# SCH_mini-arcade_2026-02-04.net
KiCad netlist of a schematic drawn in EasyEDA
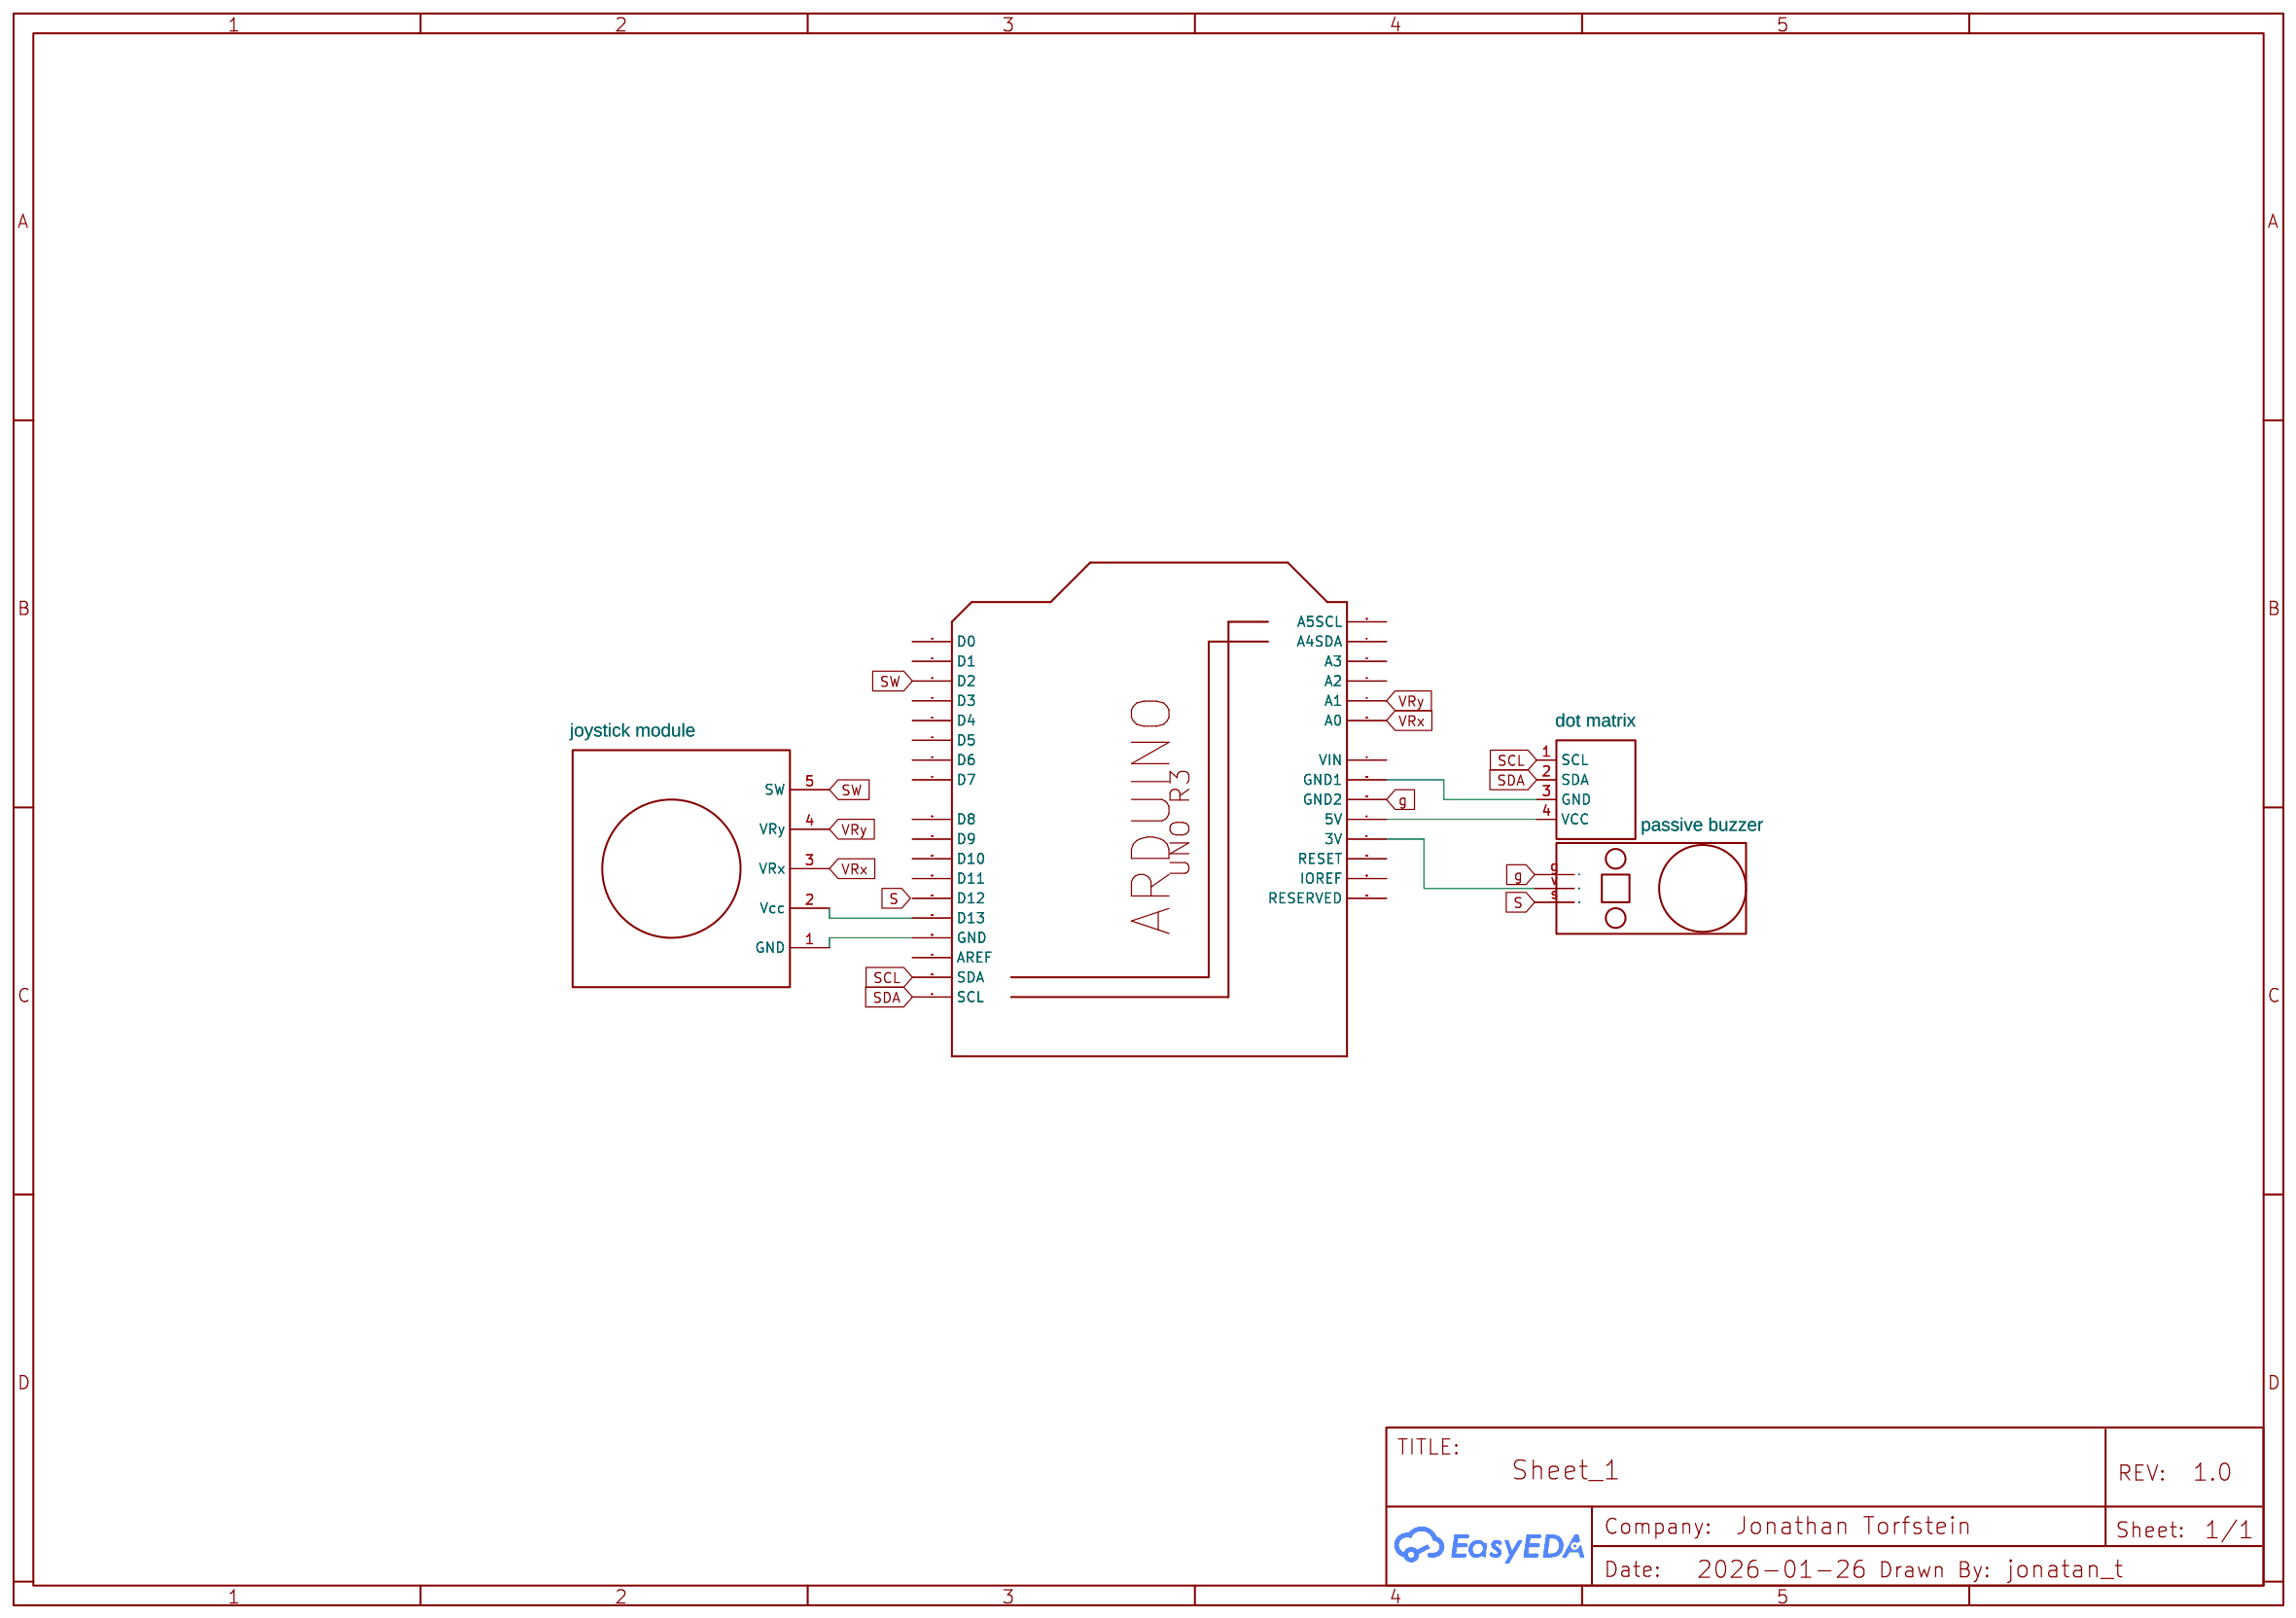
[diagram p0: schematic sheet]

(export (version "E")
  (design (tool "Eeschema 10.0.6"))
  (components
    (comp (ref "U1") (value "ARDUINOR3-DIMENSION") (libsource (lib "") (part "ARDUINOR3-DIMENSION")))
    (comp (ref "U2")
      (value "dot matrix")
      (fields
        (field (name "Manufacturer Part") "350424-1")
        (field (name "Manufacturer") "TE Connectivity(泰科电子)")
      )
      (libsource (lib "") (part "350424-1"))
    )
    (comp (ref "U3") (value "joystick module") (libsource (lib "") (part "HW-504JOYSTICK")))
    (comp (ref "U4") (value "passive buzzer") (libsource (lib "") (part "keystudio passive buzzer")))
  )
  (nets
    (net (code "1") (name "Net-(U2-GND)") (class "Default")
      (node (ref "U1") (pin "GND1") (pinfunction "GND1_GND1") (pintype "passive"))
      (node (ref "U2") (pin "3") (pinfunction "GND_3") (pintype "unspecified"))
    )
    (net (code "2") (name "Net-(U2-VCC)") (class "Default")
      (node (ref "U1") (pin "5V") (pinfunction "5V_5V") (pintype "passive"))
      (node (ref "U2") (pin "4") (pinfunction "VCC_4") (pintype "unspecified"))
    )
    (net (code "3") (name "Net-(U3-GND)") (class "Default")
      (node (ref "U1") (pin "GND") (pinfunction "GND_GND") (pintype "passive"))
      (node (ref "U3") (pin "1") (pinfunction "GND_1") (pintype "unspecified"))
    )
    (net (code "4") (name "Net-(U3-Vcc)") (class "Default")
      (node (ref "U1") (pin "D13") (pinfunction "D13_D13") (pintype "unspecified"))
      (node (ref "U3") (pin "2") (pinfunction "Vcc_2") (pintype "unspecified"))
    )
    (net (code "5") (name "Net-(U4-2)") (class "Default")
      (node (ref "U1") (pin "3V") (pinfunction "3V_3V") (pintype "passive"))
      (node (ref "U4") (pin "v") (pinfunction "2_v") (pintype "unspecified"))
    )
    (net (code "6") (name "S") (class "Default")
      (node (ref "U4") (pin "s") (pinfunction "3_s") (pintype "unspecified"))
    )
    (net (code "7") (name "SCL") (class "Default")
      (node (ref "U1") (pin "SDA") (pinfunction "SDA_SDA") (pintype "unspecified"))
      (node (ref "U2") (pin "1") (pinfunction "SCL_1") (pintype "unspecified"))
    )
    (net (code "8") (name "SDA") (class "Default")
      (node (ref "U1") (pin "SCL") (pinfunction "SCL_SCL") (pintype "unspecified"))
      (node (ref "U2") (pin "2") (pinfunction "SDA_2") (pintype "unspecified"))
    )
    (net (code "9") (name "SW") (class "Default")
      (node (ref "U1") (pin "D2") (pinfunction "D2_D2") (pintype "unspecified"))
      (node (ref "U3") (pin "5") (pinfunction "SW_5") (pintype "unspecified"))
    )
    (net (code "10") (name "VRx") (class "Default")
      (node (ref "U1") (pin "A0") (pinfunction "A0_A0") (pintype "unspecified"))
      (node (ref "U3") (pin "3") (pinfunction "VRx_3") (pintype "unspecified"))
    )
    (net (code "11") (name "VRy") (class "Default")
      (node (ref "U1") (pin "A1") (pinfunction "A1_A1") (pintype "unspecified"))
      (node (ref "U3") (pin "4") (pinfunction "VRy_4") (pintype "unspecified"))
    )
    (net (code "12") (name "g") (class "Default")
      (node (ref "U1") (pin "GND2") (pinfunction "GND2_GND2") (pintype "passive"))
      (node (ref "U4") (pin "g") (pinfunction "1_g") (pintype "unspecified"))
    )
    (net (code "13") (name "unconnected-(U1-A4SDA-PadA4)") (class "Default")
      (node (ref "U1") (pin "A4") (pinfunction "A4SDA_A4") (pintype "unspecified"))
    )
    (net (code "14") (name "unconnected-(U1-A5SCL-PadA5)") (class "Default")
      (node (ref "U1") (pin "A5") (pinfunction "A5SCL_A5") (pintype "unspecified"))
    )
    (net (code "15") (name "unconnected-(U1-PadA2)") (class "Default")
      (node (ref "U1") (pin "A2") (pinfunction "A2_A2") (pintype "unspecified"))
    )
    (net (code "16") (name "unconnected-(U1-PadA3)") (class "Default")
      (node (ref "U1") (pin "A3") (pinfunction "A3_A3") (pintype "unspecified"))
    )
    (net (code "17") (name "unconnected-(U1-PadAREF)") (class "Default")
      (node (ref "U1") (pin "AREF") (pinfunction "AREF_AREF") (pintype "unspecified"))
    )
    (net (code "18") (name "unconnected-(U1-PadD0)") (class "Default")
      (node (ref "U1") (pin "D0") (pinfunction "D0_D0") (pintype "unspecified"))
    )
    (net (code "19") (name "unconnected-(U1-PadD1)") (class "Default")
      (node (ref "U1") (pin "D1") (pinfunction "D1_D1") (pintype "unspecified"))
    )
    (net (code "20") (name "unconnected-(U1-PadD3)") (class "Default")
      (node (ref "U1") (pin "D3") (pinfunction "D3_D3") (pintype "unspecified"))
    )
    (net (code "21") (name "unconnected-(U1-PadD4)") (class "Default")
      (node (ref "U1") (pin "D4") (pinfunction "D4_D4") (pintype "unspecified"))
    )
    (net (code "22") (name "unconnected-(U1-PadD5)") (class "Default")
      (node (ref "U1") (pin "D5") (pinfunction "D5_D5") (pintype "unspecified"))
    )
    (net (code "23") (name "unconnected-(U1-PadD6)") (class "Default")
      (node (ref "U1") (pin "D6") (pinfunction "D6_D6") (pintype "unspecified"))
    )
    (net (code "24") (name "unconnected-(U1-PadD7)") (class "Default")
      (node (ref "U1") (pin "D7") (pinfunction "D7_D7") (pintype "unspecified"))
    )
    (net (code "25") (name "unconnected-(U1-PadD8)") (class "Default")
      (node (ref "U1") (pin "D8") (pinfunction "D8_D8") (pintype "unspecified"))
    )
    (net (code "26") (name "unconnected-(U1-PadD9)") (class "Default")
      (node (ref "U1") (pin "D9") (pinfunction "D9_D9") (pintype "unspecified"))
    )
    (net (code "27") (name "unconnected-(U1-PadD10)") (class "Default")
      (node (ref "U1") (pin "D10") (pinfunction "D10_D10") (pintype "unspecified"))
    )
    (net (code "28") (name "unconnected-(U1-PadD11)") (class "Default")
      (node (ref "U1") (pin "D11") (pinfunction "D11_D11") (pintype "unspecified"))
    )
    (net (code "29") (name "unconnected-(U1-PadD12)") (class "Default")
      (node (ref "U1") (pin "D12") (pinfunction "D12_D12") (pintype "unspecified"))
    )
    (net (code "30") (name "unconnected-(U1-PadIOREF)") (class "Default")
      (node (ref "U1") (pin "IOREF") (pinfunction "IOREF_IOREF") (pintype "output"))
    )
    (net (code "31") (name "unconnected-(U1-PadRESERVED)") (class "Default")
      (node (ref "U1") (pin "RESERVED") (pinfunction "RESERVED_RESERVED") (pintype "unspecified"))
    )
    (net (code "32") (name "unconnected-(U1-PadRESET)") (class "Default")
      (node (ref "U1") (pin "RESET") (pinfunction "RESET_RESET") (pintype "unspecified"))
    )
    (net (code "33") (name "unconnected-(U1-PadVIN)") (class "Default")
      (node (ref "U1") (pin "VIN") (pinfunction "VIN_VIN") (pintype "passive"))
    )
  )
)
